# RTC_Amiga_kulamario_yahoo_ie.net
KiCad netlist of a schematic drawn in EAGLE
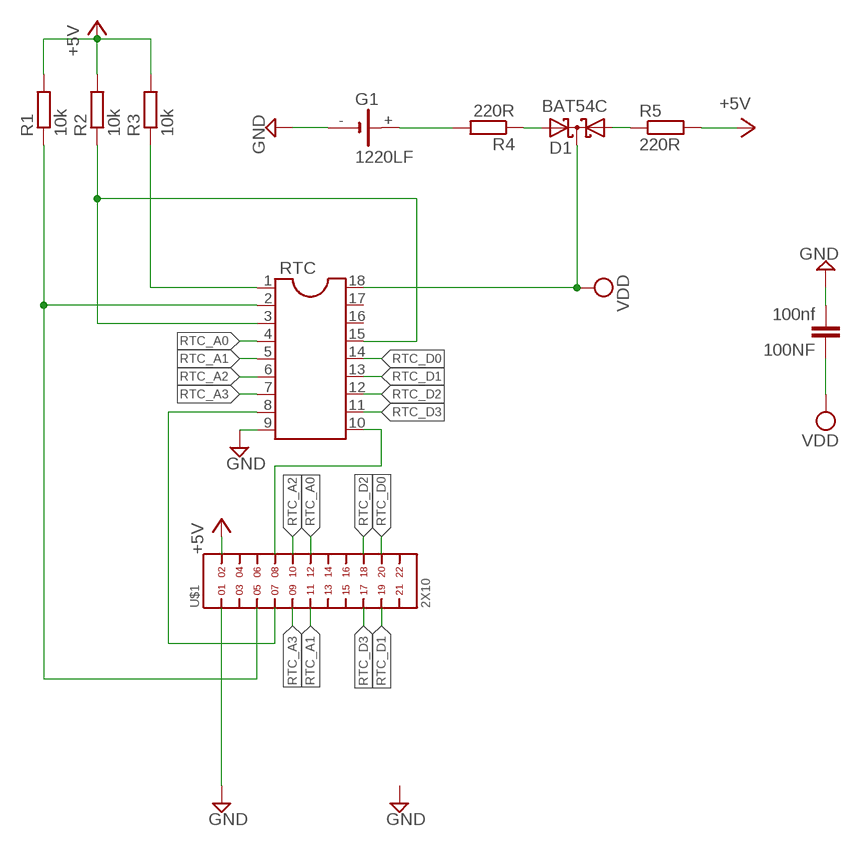
[diagram p0: schematic, sheet 1]

(export (version "E")
  (design (tool "Eeschema 10.0.6"))
  (components
    (comp (ref "100NF")
      (value "100nf")
      (footprint "eagle-import:C0603")
      (libsource (lib "eagle-import") (part "C-EUC0603"))
    )
    (comp (ref "D1")
      (value "BAT54C")
      (footprint "eagle-import:SOT23")
      (libsource (lib "eagle-import") (part "BAT54C"))
    )
    (comp (ref "G1")
      (value "1220LF")
      (footprint "eagle-import:CH291-1220LF")
      (libsource (lib "eagle-import") (part "CH291-1220LF"))
    )
    (comp (ref "R1")
      (value "10k")
      (footprint "eagle-import:R0603")
      (libsource (lib "eagle-import") (part "R-EU_R0603"))
    )
    (comp (ref "R2")
      (value "10k")
      (footprint "eagle-import:R0603")
      (libsource (lib "eagle-import") (part "R-EU_R0603"))
    )
    (comp (ref "R3")
      (value "10k")
      (footprint "eagle-import:R0603")
      (libsource (lib "eagle-import") (part "R-EU_R0603"))
    )
    (comp (ref "R4")
      (value "220R")
      (footprint "eagle-import:R0603")
      (libsource (lib "eagle-import") (part "R-EU_R0603"))
    )
    (comp (ref "R5")
      (value "220R")
      (footprint "eagle-import:R0603")
      (libsource (lib "eagle-import") (part "R-EU_R0603"))
    )
    (comp (ref "RTC")
      (value "DIL18")
      (footprint "eagle-import:DIL18")
      (libsource (lib "eagle-import") (part "DIL18"))
    )
    (comp (ref "U$1")
      (value "2X10")
      (footprint "eagle-import:2X10")
      (libsource (lib "eagle-import") (part "2X10"))
    )
  )
  (nets
    (net (code "1") (name "+5V") (class "Default")
      (node (ref "R1") (pin "2") (pinfunction "2_2") (pintype "passive"))
      (node (ref "R2") (pin "2") (pinfunction "2_2") (pintype "passive"))
      (node (ref "R3") (pin "2") (pinfunction "2_2") (pintype "passive"))
      (node (ref "R5") (pin "2") (pinfunction "2_2") (pintype "passive"))
      (node (ref "U$1") (pin "2") (pinfunction "2_2") (pintype "bidirectional"))
    )
    (net (code "2") (name "GND") (class "Default")
      (node (ref "100NF") (pin "2") (pinfunction "2_2") (pintype "passive"))
      (node (ref "G1") (pin "-") (pinfunction "-_-") (pintype "passive"))
      (node (ref "RTC") (pin "9") (pinfunction "9_9") (pintype "passive"))
      (node (ref "U$1") (pin "1") (pinfunction "1_1") (pintype "bidirectional"))
    )
    (net (code "3") (name "Net-(D1-A1)") (class "Default")
      (node (ref "D1") (pin "1") (pinfunction "A1_1") (pintype "passive"))
      (node (ref "R5") (pin "1") (pinfunction "1_1") (pintype "passive"))
    )
    (net (code "4") (name "Net-(D1-A2)") (class "Default")
      (node (ref "D1") (pin "2") (pinfunction "A2_2") (pintype "passive"))
      (node (ref "R4") (pin "1") (pinfunction "1_1") (pintype "passive"))
    )
    (net (code "5") (name "Net-(G1-Pad+)") (class "Default")
      (node (ref "G1") (pin "+") (pinfunction "+_+") (pintype "passive"))
      (node (ref "R4") (pin "2") (pinfunction "2_2") (pintype "passive"))
    )
    (net (code "6") (name "Net-(R1-Pad1)") (class "Default")
      (node (ref "R1") (pin "1") (pinfunction "1_1") (pintype "passive"))
      (node (ref "RTC") (pin "2") (pinfunction "2_2") (pintype "passive"))
      (node (ref "U$1") (pin "5") (pinfunction "5_5") (pintype "bidirectional"))
    )
    (net (code "7") (name "Net-(R2-Pad1)") (class "Default")
      (node (ref "R2") (pin "1") (pinfunction "1_1") (pintype "passive"))
      (node (ref "RTC") (pin "15") (pinfunction "15_15") (pintype "passive"))
      (node (ref "RTC") (pin "3") (pinfunction "3_3") (pintype "passive"))
    )
    (net (code "8") (name "Net-(R3-Pad1)") (class "Default")
      (node (ref "R3") (pin "1") (pinfunction "1_1") (pintype "passive"))
      (node (ref "RTC") (pin "1") (pinfunction "1_1") (pintype "passive"))
    )
    (net (code "9") (name "Net-(RTC-Pad8)") (class "Default")
      (node (ref "RTC") (pin "8") (pinfunction "8_8") (pintype "passive"))
      (node (ref "U$1") (pin "7") (pinfunction "7_7") (pintype "bidirectional"))
    )
    (net (code "10") (name "Net-(RTC-Pad10)") (class "Default")
      (node (ref "RTC") (pin "10") (pinfunction "10_10") (pintype "passive"))
      (node (ref "U$1") (pin "8") (pinfunction "8_8") (pintype "bidirectional"))
    )
    (net (code "11") (name "RTC_A0") (class "Default")
      (node (ref "RTC") (pin "4") (pinfunction "4_4") (pintype "passive"))
      (node (ref "U$1") (pin "12") (pinfunction "12_12") (pintype "bidirectional"))
    )
    (net (code "12") (name "RTC_A1") (class "Default")
      (node (ref "RTC") (pin "5") (pinfunction "5_5") (pintype "passive"))
      (node (ref "U$1") (pin "11") (pinfunction "11_11") (pintype "bidirectional"))
    )
    (net (code "13") (name "RTC_A2") (class "Default")
      (node (ref "RTC") (pin "6") (pinfunction "6_6") (pintype "passive"))
      (node (ref "U$1") (pin "10") (pinfunction "10_10") (pintype "bidirectional"))
    )
    (net (code "14") (name "RTC_A3") (class "Default")
      (node (ref "RTC") (pin "7") (pinfunction "7_7") (pintype "passive"))
      (node (ref "U$1") (pin "9") (pinfunction "9_9") (pintype "bidirectional"))
    )
    (net (code "15") (name "RTC_D0") (class "Default")
      (node (ref "RTC") (pin "14") (pinfunction "14_14") (pintype "passive"))
      (node (ref "U$1") (pin "20") (pinfunction "20_20") (pintype "bidirectional"))
    )
    (net (code "16") (name "RTC_D1") (class "Default")
      (node (ref "RTC") (pin "13") (pinfunction "13_13") (pintype "passive"))
      (node (ref "U$1") (pin "19") (pinfunction "19_19") (pintype "bidirectional"))
    )
    (net (code "17") (name "RTC_D2") (class "Default")
      (node (ref "RTC") (pin "12") (pinfunction "12_12") (pintype "passive"))
      (node (ref "U$1") (pin "18") (pinfunction "18_18") (pintype "bidirectional"))
    )
    (net (code "18") (name "RTC_D3") (class "Default")
      (node (ref "RTC") (pin "11") (pinfunction "11_11") (pintype "passive"))
      (node (ref "U$1") (pin "17") (pinfunction "17_17") (pintype "bidirectional"))
    )
    (net (code "19") (name "VDD") (class "Default")
      (node (ref "100NF") (pin "1") (pinfunction "1_1") (pintype "passive"))
      (node (ref "D1") (pin "3") (pinfunction "CC_3") (pintype "passive"))
      (node (ref "RTC") (pin "18") (pinfunction "18_18") (pintype "passive"))
    )
    (net (code "20") (name "unconnected-(RTC-Pad16)") (class "Default")
      (node (ref "RTC") (pin "16") (pinfunction "16_16") (pintype "passive"))
    )
    (net (code "21") (name "unconnected-(RTC-Pad17)") (class "Default")
      (node (ref "RTC") (pin "17") (pinfunction "17_17") (pintype "passive"))
    )
    (net (code "22") (name "unconnected-(U$1-P$1-Pad21)") (class "Default")
      (node (ref "U$1") (pin "21") (pinfunction "P$1_21") (pintype "bidirectional"))
    )
    (net (code "23") (name "unconnected-(U$1-P$2-Pad22)") (class "Default")
      (node (ref "U$1") (pin "22") (pinfunction "P$2_22") (pintype "bidirectional"))
    )
    (net (code "24") (name "unconnected-(U$1-Pad3)") (class "Default")
      (node (ref "U$1") (pin "3") (pinfunction "3_3") (pintype "bidirectional"))
    )
    (net (code "25") (name "unconnected-(U$1-Pad4)") (class "Default")
      (node (ref "U$1") (pin "4") (pinfunction "4_4") (pintype "bidirectional"))
    )
    (net (code "26") (name "unconnected-(U$1-Pad6)") (class "Default")
      (node (ref "U$1") (pin "6") (pinfunction "6_6") (pintype "bidirectional"))
    )
    (net (code "27") (name "unconnected-(U$1-Pad13)") (class "Default")
      (node (ref "U$1") (pin "13") (pinfunction "13_13") (pintype "bidirectional"))
    )
    (net (code "28") (name "unconnected-(U$1-Pad14)") (class "Default")
      (node (ref "U$1") (pin "14") (pinfunction "14_14") (pintype "bidirectional"))
    )
    (net (code "29") (name "unconnected-(U$1-Pad15)") (class "Default")
      (node (ref "U$1") (pin "15") (pinfunction "15_15") (pintype "bidirectional"))
    )
    (net (code "30") (name "unconnected-(U$1-Pad16)") (class "Default")
      (node (ref "U$1") (pin "16") (pinfunction "16_16") (pintype "bidirectional"))
    )
  )
)
